# PWR.net
KiCad netlist of a schematic drawn in Altium Designer
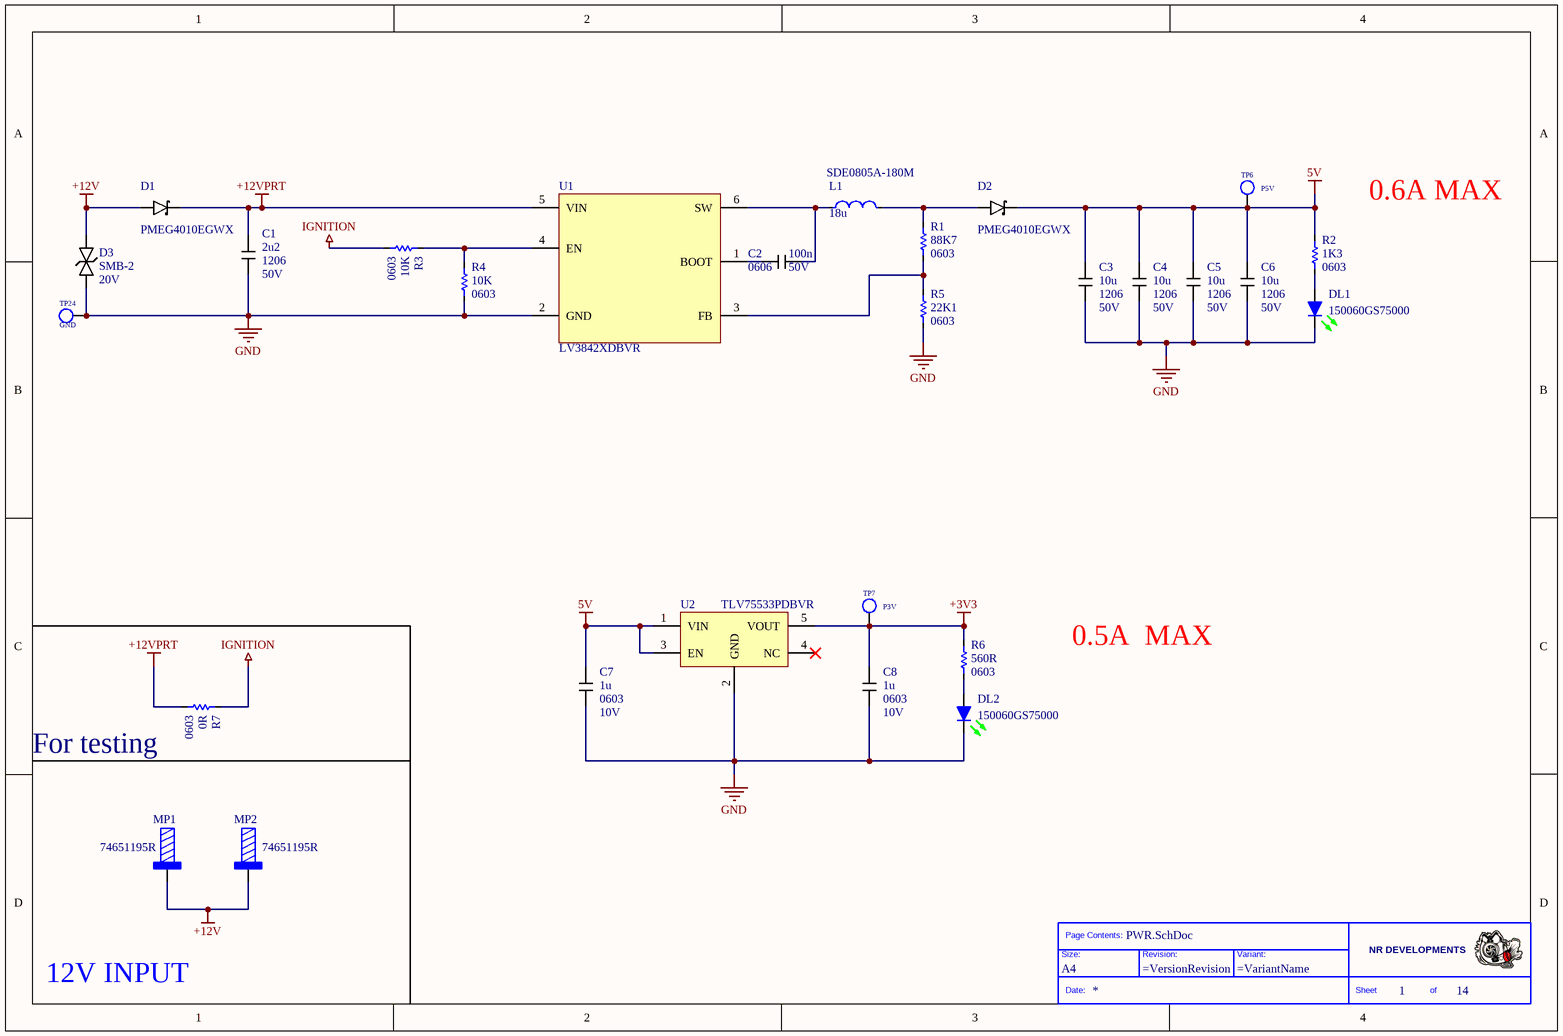
[diagram p0: PWR.SchDoc]

(export (version "E")
  (design (tool "Eeschema 10.0.6"))
  (components
    (comp (ref "C1")
      (value "2u2")
      (footprint "CAPC3216X16M")
      (fields
        (field (name "CASE") "1206")
        (field (name "VOLTAGE") "50V")
        (field (name "MANUFACTURER") "KEMET")
        (field (name "PARTNUMBER") "C1206C225K5RAC")
        (field (name "Comment") "CAP")
      )
      (libsource (lib "My_LIB") (part "CAP"))
    )
    (comp (ref "C2")
      (value "100n")
      (footprint "CAPC1608X09M")
      (fields
        (field (name "CASE") "0606")
        (field (name "VOLTAGE") "50V")
        (field (name "MANUFACTURER") "KEMET")
        (field (name "PARTNUMBER") "C0603C104K5RACTU")
        (field (name "Comment") "CAP")
      )
      (libsource (lib "My_LIB") (part "CAP"))
    )
    (comp (ref "C3")
      (value "10u")
      (footprint "CAPC3216X16M")
      (fields
        (field (name "CASE") "1206")
        (field (name "VOLTAGE") "50V")
        (field (name "MANUFACTURER") "Samsung Electro-Mechanics")
        (field (name "PARTNUMBER") "CL31B106KBHNNNE")
        (field (name "Comment") "CAP")
      )
      (libsource (lib "My_LIB") (part "CAP"))
    )
    (comp (ref "C4")
      (value "10u")
      (footprint "CAPC3216X16M")
      (fields
        (field (name "CASE") "1206")
        (field (name "VOLTAGE") "50V")
        (field (name "MANUFACTURER") "Samsung Electro-Mechanics")
        (field (name "PARTNUMBER") "CL31B106KBHNNNE")
        (field (name "Comment") "CAP")
      )
      (libsource (lib "My_LIB") (part "CAP"))
    )
    (comp (ref "C5")
      (value "10u")
      (footprint "CAPC3216X16M")
      (fields
        (field (name "CASE") "1206")
        (field (name "VOLTAGE") "50V")
        (field (name "MANUFACTURER") "Samsung Electro-Mechanics")
        (field (name "PARTNUMBER") "CL31B106KBHNNNE")
        (field (name "Comment") "CAP")
      )
      (libsource (lib "My_LIB") (part "CAP"))
    )
    (comp (ref "C6")
      (value "10u")
      (footprint "CAPC3216X16M")
      (fields
        (field (name "CASE") "1206")
        (field (name "VOLTAGE") "50V")
        (field (name "MANUFACTURER") "Samsung Electro-Mechanics")
        (field (name "PARTNUMBER") "CL31B106KBHNNNE")
        (field (name "Comment") "CAP")
      )
      (libsource (lib "My_LIB") (part "CAP"))
    )
    (comp (ref "C7")
      (value "1u")
      (footprint "CAPC1608X09M")
      (fields
        (field (name "CASE") "0603")
        (field (name "VOLTAGE") "10V")
        (field (name "MANUFACTURER") "KEMET")
        (field (name "PARTNUMBER") "C0603C105K8RACTU")
        (field (name "Comment") "CAP")
      )
      (libsource (lib "My_LIB") (part "CAP"))
    )
    (comp (ref "C8")
      (value "1u")
      (footprint "CAPC1608X09M")
      (fields
        (field (name "CASE") "0603")
        (field (name "VOLTAGE") "10V")
        (field (name "MANUFACTURER") "KEMET")
        (field (name "PARTNUMBER") "C0603C105K8RACTU")
        (field (name "Comment") "CAP")
      )
      (libsource (lib "My_LIB") (part "CAP"))
    )
    (comp (ref "D1")
      (value "PMEG4010EGWX")
      (footprint "SODFL360X130-2M -AC")
      (fields (field (name "MANUFACTURER") "Nexperia") (field (name "Comment") "Diode_Schottky"))
      (libsource (lib "My_LIB") (part "Diode_Schottky"))
    )
    (comp (ref "D2")
      (value "PMEG4010EGWX")
      (footprint "SODFL360X130-2M -AC")
      (fields (field (name "MANUFACTURER") "Nexperia") (field (name "Comment") "Diode_Schottky"))
      (libsource (lib "My_LIB") (part "Diode_Schottky"))
    )
    (comp (ref "D3")
      (value "Diode")
      (footprint "ONSC-SMB-2")
      (fields
        (field (name "CASE") "SMB-2")
        (field (name "VOLTAGE") "20V")
        (field (name "MANUFACTURER") "Littelfuse")
        (field (name "PARTNUMBER") "SZ1SMB20CAT3G")
      )
      (libsource (lib "My_LIB") (part "Diode_TVS_Bid"))
    )
    (comp (ref "DL1")
      (value "150060GS75000")
      (footprint "LED0603")
      (fields (field (name "MANUFACTURER") "Wurth Elektronik") (field (name "Comment") "LED_Green"))
      (libsource (lib "My_LIB") (part "LED_Green"))
    )
    (comp (ref "DL2")
      (value "150060GS75000")
      (footprint "LED0603")
      (fields (field (name "MANUFACTURER") "Wurth Elektronik") (field (name "Comment") "LED_Green"))
      (libsource (lib "My_LIB") (part "LED_Green"))
    )
    (comp (ref "L1")
      (value "18u")
      (footprint "BOURNS_SDE0805A")
      (fields
        (field (name "MANUFACTURER") "BOURNS")
        (field (name "PARTNUMBER") "SDE0805A-180M")
        (field (name "Comment") "IND")
      )
      (libsource (lib "My_LIB") (part "IND"))
    )
    (comp (ref "MP1")
      (value "74651195R")
      (footprint "WURTH_74651195")
      (fields (field (name "MANUFACTURER") "Wurth Electronics") (field (name "Comment") "Connector"))
      (libsource (lib "My_LIB") (part "74651195R"))
    )
    (comp (ref "MP2")
      (value "74651195R")
      (footprint "WURTH_74651195")
      (fields (field (name "MANUFACTURER") "Wurth Electronics") (field (name "Comment") "Connector"))
      (libsource (lib "My_LIB") (part "74651195R"))
    )
    (comp (ref "R1")
      (value "88K7")
      (footprint "RESC1608X06M")
      (fields
        (field (name "CASE") "0603")
        (field (name "MANUFACTURER") "Vishay")
        (field (name "PARTNUMBER") "CRCW060388K7FKEAC")
        (field (name "Comment") "Res")
      )
      (libsource (lib "My_LIB") (part "Resistor"))
    )
    (comp (ref "R2")
      (value "1K3")
      (footprint "RESC1608X06M")
      (fields
        (field (name "CASE") "0603")
        (field (name "MANUFACTURER") "Vishay")
        (field (name "PARTNUMBER") "RC0603FR-071K3L")
        (field (name "Comment") "Res")
      )
      (libsource (lib "My_LIB") (part "Resistor"))
    )
    (comp (ref "R3")
      (value "10K")
      (footprint "RESC1608X06M")
      (fields
        (field (name "CASE") "0603")
        (field (name "MANUFACTURER") "YAGEO")
        (field (name "PARTNUMBER") "AC0603FR-0710KL")
        (field (name "Comment") "Res")
      )
      (libsource (lib "My_LIB") (part "Resistor"))
    )
    (comp (ref "R4")
      (value "10K")
      (footprint "RESC1608X06M")
      (fields
        (field (name "CASE") "0603")
        (field (name "MANUFACTURER") "YAGEO")
        (field (name "PARTNUMBER") "AC0603FR-0710KL")
        (field (name "Comment") "Res")
      )
      (libsource (lib "My_LIB") (part "Resistor"))
    )
    (comp (ref "R5")
      (value "22K1")
      (footprint "RESC1608X06M")
      (fields
        (field (name "CASE") "0603")
        (field (name "MANUFACTURER") "Vishay")
        (field (name "PARTNUMBER") "CRCW060322K1FKEA")
        (field (name "Comment") "Res")
      )
      (libsource (lib "My_LIB") (part "Resistor"))
    )
    (comp (ref "R6")
      (value "560R")
      (footprint "RESC1608X06M")
      (fields
        (field (name "CASE") "0603")
        (field (name "MANUFACTURER") "Vishay")
        (field (name "PARTNUMBER") "RC0603FR-07560RL")
        (field (name "Comment") "Res")
      )
      (libsource (lib "My_LIB") (part "Resistor"))
    )
    (comp (ref "R7")
      (value "0R")
      (footprint "RESC1608X06M")
      (fields
        (field (name "CASE") "0603")
        (field (name "MANUFACTURER") "YAGEO")
        (field (name "PARTNUMBER") "RC0603JR-070RL")
        (field (name "Comment") "Res")
      )
      (libsource (lib "My_LIB") (part "Resistor"))
    )
    (comp (ref "TP6") (value "P5V") (footprint "TP_c200") (libsource (lib "My_LIB") (part "Test_Point")))
    (comp (ref "TP7") (value "P3V") (footprint "TP_c200") (libsource (lib "My_LIB") (part "Test_Point")))
    (comp (ref "TP24") (value "GND") (footprint "TP_c200") (libsource (lib "My_LIB") (part "Test_Point")))
    (comp (ref "U1")
      (value "LV3842XDBVR")
      (footprint "SOT95P280X145-6N")
      (description "4-V to 36-V, 600-mA synchronous step-down converter")
      (fields (field (name "MANUFACTURER") "Texas Instruments") (field (name "Comment") "DC DC"))
      (libsource (lib "My_LIB") (part "LV3842XDBVR"))
    )
    (comp (ref "U2")
      (value "TLV75533PDBVR")
      (footprint "SOT95P280X145-5N")
      (description "LDO Voltage Regulators 500-mA high-PSRR low-IQ low-dropout voltage regulator with enable")
      (fields (field (name "MANUFACTURER") "Texas Instruments") (field (name "Comment") "TLV75530PDBVR"))
      (libsource (lib "My_LIB") (part "TLV75530PDBVR"))
    )
  )
  (nets
    (net (code "1") (name "+3V3") (class "Default")
      (node (ref "C8") (pin "1") (pinfunction "1_1") (pintype "passive"))
      (node (ref "R6") (pin "2") (pinfunction "2_2") (pintype "passive"))
      (node (ref "TP7") (pin "1") (pinfunction "1_1") (pintype "passive"))
      (node (ref "U2") (pin "5") (pinfunction "VOUT_5") (pintype "power_in"))
    )
    (net (code "2") (name "+12V") (class "Default")
      (node (ref "D1") (pin "A") (pinfunction "A_A") (pintype "passive"))
      (node (ref "D3") (pin "2") (pinfunction "2_2") (pintype "passive"))
      (node (ref "MP1") (pin "1") (pinfunction "1_1") (pintype "passive"))
      (node (ref "MP2") (pin "1") (pinfunction "1_1") (pintype "passive"))
    )
    (net (code "3") (name "+12VPRT") (class "Default")
      (node (ref "C1") (pin "1") (pinfunction "1_1") (pintype "passive"))
      (node (ref "D1") (pin "C") (pinfunction "C_C") (pintype "passive"))
      (node (ref "R7") (pin "1") (pinfunction "1_1") (pintype "passive"))
      (node (ref "U1") (pin "5") (pinfunction "VIN_5") (pintype "power_in"))
    )
    (net (code "4") (name "5V") (class "Default")
      (node (ref "C3") (pin "1") (pinfunction "1_1") (pintype "passive"))
      (node (ref "C4") (pin "1") (pinfunction "1_1") (pintype "passive"))
      (node (ref "C5") (pin "1") (pinfunction "1_1") (pintype "passive"))
      (node (ref "C6") (pin "1") (pinfunction "1_1") (pintype "passive"))
      (node (ref "C7") (pin "1") (pinfunction "1_1") (pintype "passive"))
      (node (ref "D2") (pin "C") (pinfunction "C_C") (pintype "passive"))
      (node (ref "R2") (pin "2") (pinfunction "2_2") (pintype "passive"))
      (node (ref "TP6") (pin "1") (pinfunction "1_1") (pintype "passive"))
      (node (ref "U2") (pin "1") (pinfunction "VIN_1") (pintype "power_in"))
      (node (ref "U2") (pin "3") (pinfunction "EN_3") (pintype "passive"))
    )
    (net (code "5") (name "GND") (class "Default")
      (node (ref "C1") (pin "2") (pinfunction "2_2") (pintype "passive"))
      (node (ref "C3") (pin "2") (pinfunction "2_2") (pintype "passive"))
      (node (ref "C4") (pin "2") (pinfunction "2_2") (pintype "passive"))
      (node (ref "C5") (pin "2") (pinfunction "2_2") (pintype "passive"))
      (node (ref "C6") (pin "2") (pinfunction "2_2") (pintype "passive"))
      (node (ref "C7") (pin "2") (pinfunction "2_2") (pintype "passive"))
      (node (ref "C8") (pin "2") (pinfunction "2_2") (pintype "passive"))
      (node (ref "D3") (pin "1") (pinfunction "1_1") (pintype "passive"))
      (node (ref "DL1") (pin "C") (pinfunction "C_C") (pintype "passive"))
      (node (ref "DL2") (pin "C") (pinfunction "C_C") (pintype "passive"))
      (node (ref "R4") (pin "1") (pinfunction "1_1") (pintype "passive"))
      (node (ref "R5") (pin "1") (pinfunction "1_1") (pintype "passive"))
      (node (ref "TP24") (pin "1") (pinfunction "1_1") (pintype "passive"))
      (node (ref "U1") (pin "2") (pinfunction "GND_2") (pintype "power_in"))
      (node (ref "U2") (pin "2") (pinfunction "GND_2") (pintype "power_in"))
    )
    (net (code "6") (name "IGNITION") (class "Default")
      (node (ref "R3") (pin "1") (pinfunction "1_1") (pintype "passive"))
      (node (ref "R7") (pin "2") (pinfunction "2_2") (pintype "passive"))
    )
    (net (code "7") (name "Net-(D2-PadA)") (class "Default")
      (node (ref "D2") (pin "A") (pinfunction "A_A") (pintype "passive"))
      (node (ref "L1") (pin "2") (pinfunction "2_2") (pintype "passive"))
      (node (ref "R1") (pin "2") (pinfunction "2_2") (pintype "passive"))
    )
    (net (code "8") (name "Net-(DL1-PadA)") (class "Default")
      (node (ref "DL1") (pin "A") (pinfunction "A_A") (pintype "passive"))
      (node (ref "R2") (pin "1") (pinfunction "1_1") (pintype "passive"))
    )
    (net (code "9") (name "Net-(DL2-PadA)") (class "Default")
      (node (ref "DL2") (pin "A") (pinfunction "A_A") (pintype "passive"))
      (node (ref "R6") (pin "1") (pinfunction "1_1") (pintype "passive"))
    )
    (net (code "10") (name "Net-(U1-BOOT)") (class "Default")
      (node (ref "C2") (pin "1") (pinfunction "1_1") (pintype "passive"))
      (node (ref "U1") (pin "1") (pinfunction "BOOT_1") (pintype "power_in"))
    )
    (net (code "11") (name "Net-(U1-EN)") (class "Default")
      (node (ref "R3") (pin "2") (pinfunction "2_2") (pintype "passive"))
      (node (ref "R4") (pin "2") (pinfunction "2_2") (pintype "passive"))
      (node (ref "U1") (pin "4") (pinfunction "EN_4") (pintype "passive"))
    )
    (net (code "12") (name "Net-(U1-FB)") (class "Default")
      (node (ref "R1") (pin "1") (pinfunction "1_1") (pintype "passive"))
      (node (ref "R5") (pin "2") (pinfunction "2_2") (pintype "passive"))
      (node (ref "U1") (pin "3") (pinfunction "FB_3") (pintype "passive"))
    )
    (net (code "13") (name "Net-(U1-SW)") (class "Default")
      (node (ref "C2") (pin "2") (pinfunction "2_2") (pintype "passive"))
      (node (ref "L1") (pin "1") (pinfunction "1_1") (pintype "passive"))
      (node (ref "U1") (pin "6") (pinfunction "SW_6") (pintype "power_in"))
    )
    (net (code "14") (name "unconnected-(U2-NC-Pad4)") (class "Default")
      (node (ref "U2") (pin "4") (pinfunction "NC_4") (pintype "passive+no_connect"))
    )
  )
)
